# Bridge.net
KiCad netlist of a schematic drawn in Altium Designer
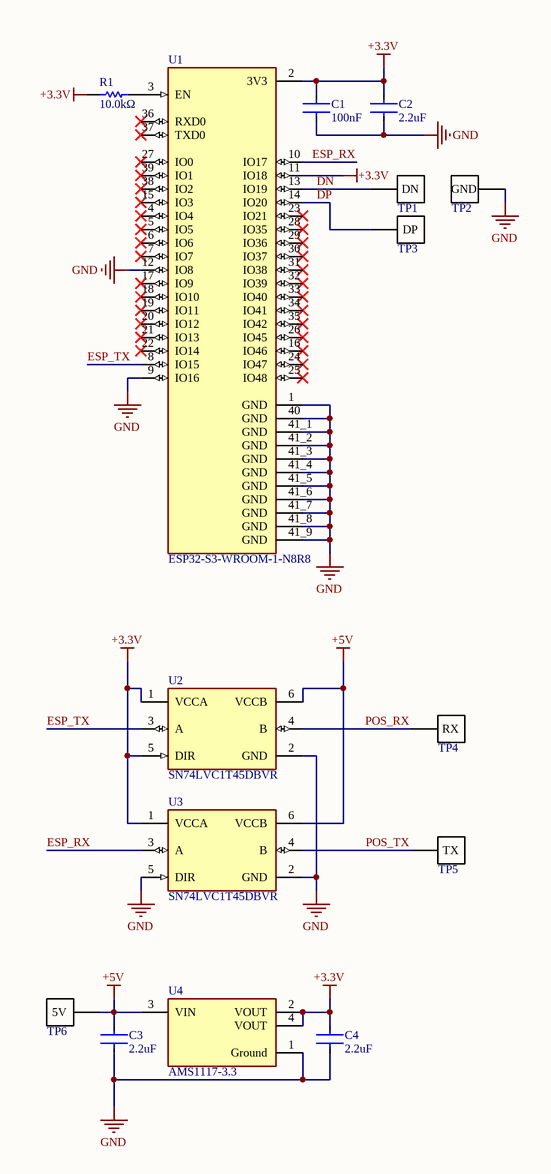
[diagram p0: Bridge.SchDoc]

(export (version "E")
  (design (tool "Eeschema 10.0.6"))
  (components
    (comp (ref "C1")
      (value "100nF")
      (footprint "FP-GRM0603-MFG")
      (description "Cap 100nF 25V X7R 0603 ±10%")
      (fields (field (name "PART NUMBER") "GRM188R71E104KA01D") (field (name "MANUFACTURER") "Murata"))
      (libsource (lib "Murata_GRM") (part "MuRata_GRM"))
    )
    (comp (ref "C2")
      (value "2.2uF")
      (footprint "FP-GRM0603-MFG")
      (description "Cap 2.2uF 10V X7R 0603 ±10%")
      (fields (field (name "PART NUMBER") "GRM188R71A225KE15D") (field (name "MANUFACTURER") "Murata"))
      (libsource (lib "Murata_GRM") (part "MuRata_GRM"))
    )
    (comp (ref "C3")
      (value "2.2uF")
      (footprint "FP-GRM0603-MFG")
      (description "Cap 2.2uF 10V X7R 0603 ±10%")
      (fields (field (name "PART NUMBER") "GRM188R71A225KE15D") (field (name "MANUFACTURER") "Murata"))
      (libsource (lib "Murata_GRM") (part "MuRata_GRM"))
    )
    (comp (ref "C4")
      (value "2.2uF")
      (footprint "FP-GRM0603-MFG")
      (description "Cap 2.2uF 10V X7R 0603 ±10%")
      (fields (field (name "PART NUMBER") "GRM188R71A225KE15D") (field (name "MANUFACTURER") "Murata"))
      (libsource (lib "Murata_GRM") (part "MuRata_GRM"))
    )
    (comp (ref "R1")
      (value "10.0kΩ")
      (footprint "FP-CRCW0603-E3-MFG")
      (description "Resistor 10.0kΩ ±5% 0603 ±200 ppm/K")
      (fields (field (name "PART NUMBER") "CRCW060310K0JN") (field (name "MANUFACTURER") "Vishay"))
      (libsource (lib "Vishay_CRC") (part "Vishay_CRC"))
    )
    (comp (ref "TP1") (value "DN") (footprint "FP-Testpoint") (libsource (lib "Pads") (part "Testpoint")))
    (comp (ref "TP2") (value "GND") (footprint "FP-Testpoint") (libsource (lib "") (part "Testpoint_1")))
    (comp (ref "TP3") (value "DP") (footprint "FP-Testpoint") (libsource (lib "Pads") (part "Testpoint")))
    (comp (ref "TP4") (value "RX") (footprint "FP-Testpoint") (libsource (lib "Pads") (part "Testpoint")))
    (comp (ref "TP5") (value "TX") (footprint "FP-Testpoint") (libsource (lib "Pads") (part "Testpoint")))
    (comp (ref "TP6") (value "5V") (footprint "FP-Testpoint") (libsource (lib "") (part "Testpoint_1")))
    (comp (ref "U1")
      (value "ESP32-S3-WROOM-1-N8R8")
      (footprint "XCVR_ESP32S3WROOM1N8R8")
      (description "Bluetooth, WiFi 802.11b/g/n, Bluetooth v5.0 Transceiver Module 2.4GHz PCB Trace Surface Mount")
      (fields (field (name "MF") "Espressif Systems"))
      (libsource (lib "ESP32-S3-WROOM-1-N8R8") (part "ESP32-S3-WROOM-1-N8R8"))
    )
    (comp (ref "U2")
      (value "SN74LVC1T45DBVR")
      (footprint "FP-DBV0006A-IPC_C")
      (description "IC TRNSLTR BIDIRECTIONAL SOT23-6")
      (libsource (lib "Altium Content Vault") (part "7317ea058f373ab919a7c78c581a60e"))
    )
    (comp (ref "U3")
      (value "SN74LVC1T45DBVR")
      (footprint "FP-DBV0006A-IPC_C")
      (description "IC TRNSLTR BIDIRECTIONAL SOT23-6")
      (libsource (lib "Altium Content Vault") (part "7317ea058f373ab919a7c78c581a60e"))
    )
    (comp (ref "U4")
      (value "AMS1117-3.3")
      (footprint "FP-AMS1117-IPC_C")
      (description "LDO Voltage Regulators 1A, 3.3V")
      (fields
        (field (name "OCTOPART") "https://octopart.com/ams1117-3.3-advanced+monolithic+systems-25899300")
        (field (name "MANUFACTURER") "Advanced Monolithic Systems")
      )
      (libsource (lib "Altium Content Vault") (part "8bdbb5f8e77002000e30dd2845d0354"))
    )
  )
  (nets
    (net (code "1") (name "+3.3V") (class "Default")
      (node (ref "C1") (pin "1") (pinfunction "1_1") (pintype "passive"))
      (node (ref "C2") (pin "1") (pinfunction "1_1") (pintype "passive"))
      (node (ref "C4") (pin "1") (pinfunction "1_1") (pintype "passive"))
      (node (ref "R1") (pin "2") (pinfunction "2_2") (pintype "passive"))
      (node (ref "U1") (pin "11") (pinfunction "IO18_11") (pintype "bidirectional"))
      (node (ref "U1") (pin "2") (pinfunction "3V3_2") (pintype "power_in"))
      (node (ref "U2") (pin "1") (pinfunction "VCCA_1") (pintype "power_in"))
      (node (ref "U2") (pin "5") (pinfunction "DIR_5") (pintype "input"))
      (node (ref "U3") (pin "1") (pinfunction "VCCA_1") (pintype "power_in"))
      (node (ref "U4") (pin "2") (pinfunction "VOUT_2") (pintype "passive"))
      (node (ref "U4") (pin "4") (pinfunction "VOUT_4") (pintype "passive"))
    )
    (net (code "2") (name "+5V") (class "Default")
      (node (ref "C3") (pin "1") (pinfunction "1_1") (pintype "passive"))
      (node (ref "TP6") (pin "1") (pinfunction "1_1") (pintype "passive"))
      (node (ref "U2") (pin "6") (pinfunction "VCCB_6") (pintype "power_in"))
      (node (ref "U3") (pin "6") (pinfunction "VCCB_6") (pintype "power_in"))
      (node (ref "U4") (pin "3") (pinfunction "VIN_3") (pintype "power_in"))
    )
    (net (code "3") (name "/DN") (class "Default")
      (node (ref "TP1") (pin "1") (pinfunction "1_1") (pintype "passive"))
      (node (ref "U1") (pin "13") (pinfunction "IO19_13") (pintype "bidirectional"))
    )
    (net (code "4") (name "/DP") (class "Default")
      (node (ref "TP3") (pin "1") (pinfunction "1_1") (pintype "passive"))
      (node (ref "U1") (pin "14") (pinfunction "IO20_14") (pintype "bidirectional"))
    )
    (net (code "5") (name "/ESP_RX") (class "Default")
      (node (ref "U1") (pin "10") (pinfunction "IO17_10") (pintype "bidirectional"))
      (node (ref "U3") (pin "3") (pinfunction "A_3") (pintype "bidirectional"))
    )
    (net (code "6") (name "/ESP_TX") (class "Default")
      (node (ref "U1") (pin "8") (pinfunction "IO15_8") (pintype "bidirectional"))
      (node (ref "U2") (pin "3") (pinfunction "A_3") (pintype "bidirectional"))
    )
    (net (code "7") (name "/POS_RX") (class "Default")
      (node (ref "TP4") (pin "1") (pinfunction "1_1") (pintype "passive"))
      (node (ref "U2") (pin "4") (pinfunction "B_4") (pintype "bidirectional"))
    )
    (net (code "8") (name "/POS_TX") (class "Default")
      (node (ref "TP5") (pin "1") (pinfunction "1_1") (pintype "passive"))
      (node (ref "U3") (pin "4") (pinfunction "B_4") (pintype "bidirectional"))
    )
    (net (code "9") (name "GND") (class "Default")
      (node (ref "C1") (pin "2") (pinfunction "2_2") (pintype "passive"))
      (node (ref "C2") (pin "2") (pinfunction "2_2") (pintype "passive"))
      (node (ref "C3") (pin "2") (pinfunction "2_2") (pintype "passive"))
      (node (ref "C4") (pin "2") (pinfunction "2_2") (pintype "passive"))
      (node (ref "TP2") (pin "1") (pinfunction "1_1") (pintype "passive"))
      (node (ref "U1") (pin "1") (pinfunction "GND_1") (pintype "power_in"))
      (node (ref "U1") (pin "12") (pinfunction "IO8_12") (pintype "bidirectional"))
      (node (ref "U1") (pin "40") (pinfunction "GND_40") (pintype "power_in"))
      (node (ref "U1") (pin "41_1") (pinfunction "GND_41_1") (pintype "power_in"))
      (node (ref "U1") (pin "41_2") (pinfunction "GND_41_2") (pintype "power_in"))
      (node (ref "U1") (pin "41_3") (pinfunction "GND_41_3") (pintype "power_in"))
      (node (ref "U1") (pin "41_4") (pinfunction "GND_41_4") (pintype "power_in"))
      (node (ref "U1") (pin "41_5") (pinfunction "GND_41_5") (pintype "power_in"))
      (node (ref "U1") (pin "41_6") (pinfunction "GND_41_6") (pintype "power_in"))
      (node (ref "U1") (pin "41_7") (pinfunction "GND_41_7") (pintype "power_in"))
      (node (ref "U1") (pin "41_8") (pinfunction "GND_41_8") (pintype "power_in"))
      (node (ref "U1") (pin "41_9") (pinfunction "GND_41_9") (pintype "power_in"))
      (node (ref "U1") (pin "9") (pinfunction "IO16_9") (pintype "bidirectional"))
      (node (ref "U2") (pin "2") (pinfunction "GND_2") (pintype "power_in"))
      (node (ref "U3") (pin "2") (pinfunction "GND_2") (pintype "power_in"))
      (node (ref "U3") (pin "5") (pinfunction "DIR_5") (pintype "input"))
      (node (ref "U4") (pin "1") (pinfunction "Ground_1") (pintype "power_in"))
    )
    (net (code "10") (name "Net-(U1-EN)") (class "Default")
      (node (ref "R1") (pin "1") (pinfunction "1_1") (pintype "passive"))
      (node (ref "U1") (pin "3") (pinfunction "EN_3") (pintype "input"))
    )
    (net (code "11") (name "unconnected-(U1-IO0-Pad27)") (class "Default")
      (node (ref "U1") (pin "27") (pinfunction "IO0_27") (pintype "bidirectional+no_connect"))
    )
    (net (code "12") (name "unconnected-(U1-IO1-Pad39)") (class "Default")
      (node (ref "U1") (pin "39") (pinfunction "IO1_39") (pintype "bidirectional+no_connect"))
    )
    (net (code "13") (name "unconnected-(U1-IO2-Pad38)") (class "Default")
      (node (ref "U1") (pin "38") (pinfunction "IO2_38") (pintype "bidirectional+no_connect"))
    )
    (net (code "14") (name "unconnected-(U1-IO3-Pad15)") (class "Default")
      (node (ref "U1") (pin "15") (pinfunction "IO3_15") (pintype "bidirectional+no_connect"))
    )
    (net (code "15") (name "unconnected-(U1-IO4-Pad4)") (class "Default")
      (node (ref "U1") (pin "4") (pinfunction "IO4_4") (pintype "bidirectional+no_connect"))
    )
    (net (code "16") (name "unconnected-(U1-IO5-Pad5)") (class "Default")
      (node (ref "U1") (pin "5") (pinfunction "IO5_5") (pintype "bidirectional+no_connect"))
    )
    (net (code "17") (name "unconnected-(U1-IO6-Pad6)") (class "Default")
      (node (ref "U1") (pin "6") (pinfunction "IO6_6") (pintype "bidirectional+no_connect"))
    )
    (net (code "18") (name "unconnected-(U1-IO7-Pad7)") (class "Default")
      (node (ref "U1") (pin "7") (pinfunction "IO7_7") (pintype "bidirectional+no_connect"))
    )
    (net (code "19") (name "unconnected-(U1-IO9-Pad17)") (class "Default")
      (node (ref "U1") (pin "17") (pinfunction "IO9_17") (pintype "bidirectional+no_connect"))
    )
    (net (code "20") (name "unconnected-(U1-IO10-Pad18)") (class "Default")
      (node (ref "U1") (pin "18") (pinfunction "IO10_18") (pintype "bidirectional+no_connect"))
    )
    (net (code "21") (name "unconnected-(U1-IO11-Pad19)") (class "Default")
      (node (ref "U1") (pin "19") (pinfunction "IO11_19") (pintype "bidirectional+no_connect"))
    )
    (net (code "22") (name "unconnected-(U1-IO12-Pad20)") (class "Default")
      (node (ref "U1") (pin "20") (pinfunction "IO12_20") (pintype "bidirectional+no_connect"))
    )
    (net (code "23") (name "unconnected-(U1-IO13-Pad21)") (class "Default")
      (node (ref "U1") (pin "21") (pinfunction "IO13_21") (pintype "bidirectional+no_connect"))
    )
    (net (code "24") (name "unconnected-(U1-IO14-Pad22)") (class "Default")
      (node (ref "U1") (pin "22") (pinfunction "IO14_22") (pintype "bidirectional+no_connect"))
    )
    (net (code "25") (name "unconnected-(U1-IO21-Pad23)") (class "Default")
      (node (ref "U1") (pin "23") (pinfunction "IO21_23") (pintype "bidirectional+no_connect"))
    )
    (net (code "26") (name "unconnected-(U1-IO35-Pad28)") (class "Default")
      (node (ref "U1") (pin "28") (pinfunction "IO35_28") (pintype "bidirectional+no_connect"))
    )
    (net (code "27") (name "unconnected-(U1-IO36-Pad29)") (class "Default")
      (node (ref "U1") (pin "29") (pinfunction "IO36_29") (pintype "bidirectional+no_connect"))
    )
    (net (code "28") (name "unconnected-(U1-IO37-Pad30)") (class "Default")
      (node (ref "U1") (pin "30") (pinfunction "IO37_30") (pintype "bidirectional+no_connect"))
    )
    (net (code "29") (name "unconnected-(U1-IO38-Pad31)") (class "Default")
      (node (ref "U1") (pin "31") (pinfunction "IO38_31") (pintype "bidirectional+no_connect"))
    )
    (net (code "30") (name "unconnected-(U1-IO39-Pad32)") (class "Default")
      (node (ref "U1") (pin "32") (pinfunction "IO39_32") (pintype "bidirectional+no_connect"))
    )
    (net (code "31") (name "unconnected-(U1-IO40-Pad33)") (class "Default")
      (node (ref "U1") (pin "33") (pinfunction "IO40_33") (pintype "bidirectional+no_connect"))
    )
    (net (code "32") (name "unconnected-(U1-IO41-Pad34)") (class "Default")
      (node (ref "U1") (pin "34") (pinfunction "IO41_34") (pintype "bidirectional+no_connect"))
    )
    (net (code "33") (name "unconnected-(U1-IO42-Pad35)") (class "Default")
      (node (ref "U1") (pin "35") (pinfunction "IO42_35") (pintype "bidirectional+no_connect"))
    )
    (net (code "34") (name "unconnected-(U1-IO45-Pad26)") (class "Default")
      (node (ref "U1") (pin "26") (pinfunction "IO45_26") (pintype "bidirectional+no_connect"))
    )
    (net (code "35") (name "unconnected-(U1-IO46-Pad16)") (class "Default")
      (node (ref "U1") (pin "16") (pinfunction "IO46_16") (pintype "bidirectional+no_connect"))
    )
    (net (code "36") (name "unconnected-(U1-IO47-Pad24)") (class "Default")
      (node (ref "U1") (pin "24") (pinfunction "IO47_24") (pintype "bidirectional+no_connect"))
    )
    (net (code "37") (name "unconnected-(U1-IO48-Pad25)") (class "Default")
      (node (ref "U1") (pin "25") (pinfunction "IO48_25") (pintype "bidirectional+no_connect"))
    )
    (net (code "38") (name "unconnected-(U1-RXD0-Pad36)") (class "Default")
      (node (ref "U1") (pin "36") (pinfunction "RXD0_36") (pintype "bidirectional+no_connect"))
    )
    (net (code "39") (name "unconnected-(U1-TXD0-Pad37)") (class "Default")
      (node (ref "U1") (pin "37") (pinfunction "TXD0_37") (pintype "bidirectional+no_connect"))
    )
  )
)
